# SOCEthernetPHY.net
KiCad netlist of a schematic drawn in Altium Designer
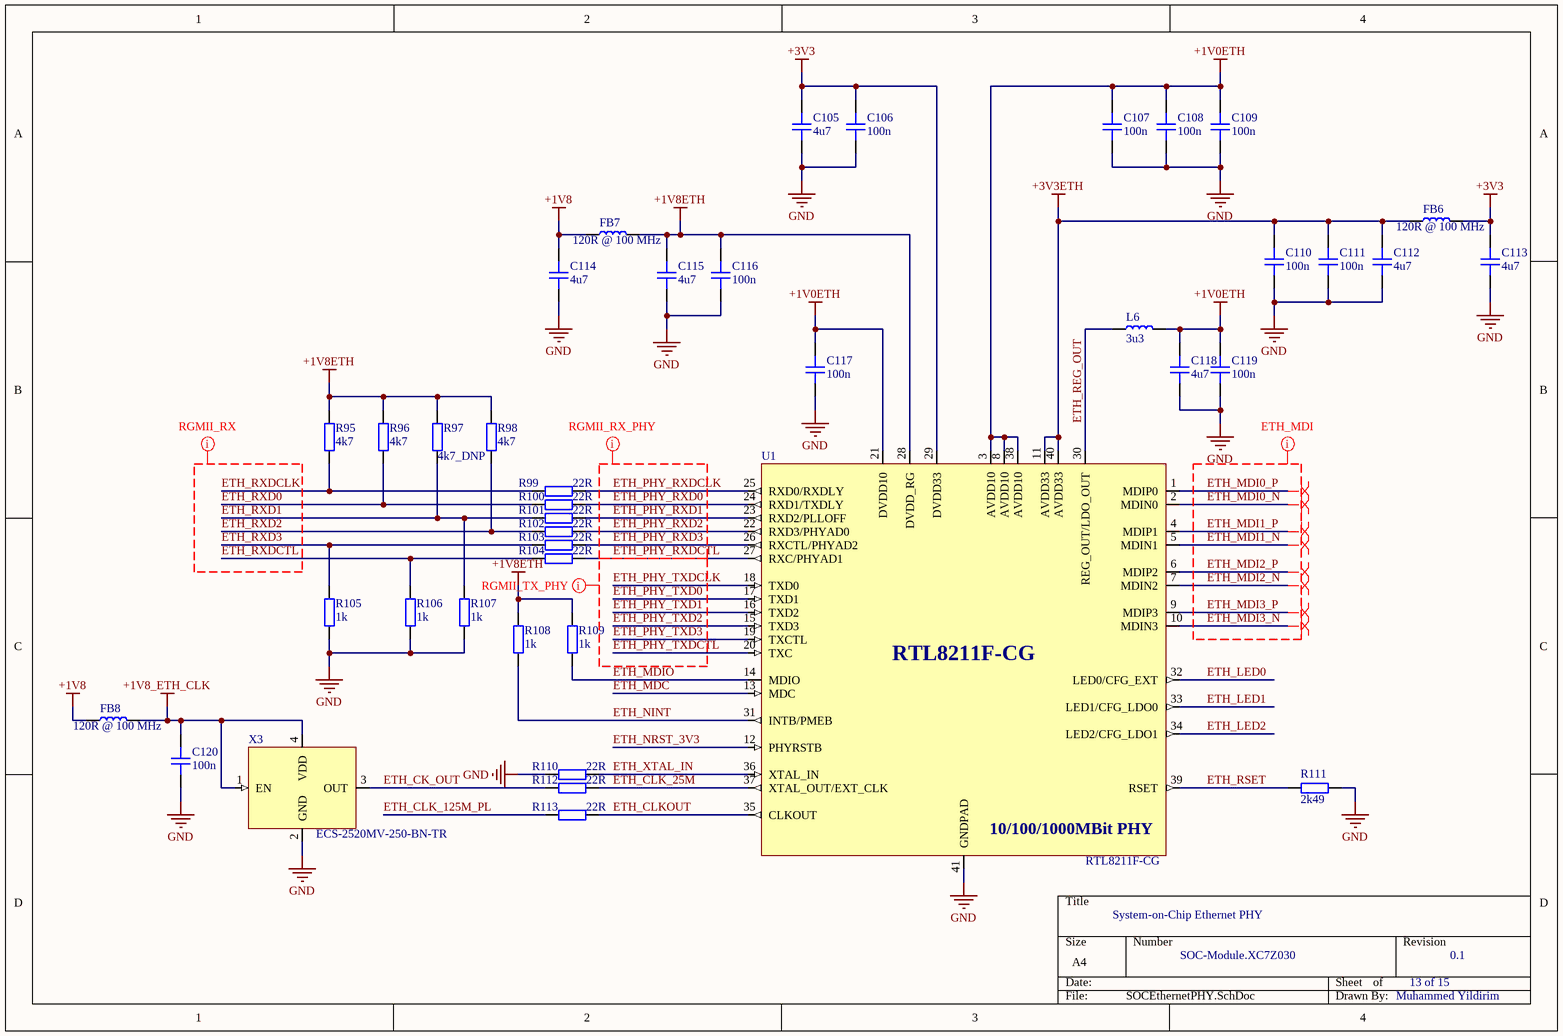
[diagram p0: SOCEthernetPHY.SchDoc]

(export (version "E")
  (design (tool "Eeschema 10.0.6"))
  (components
    (comp (ref "C105")
      (value "4u7")
      (footprint "CAP_0402")
      (description "Capacitor SMD 0402")
      (libsource (lib "Schematic-Lib-PhilsLab") (part "CAP_0402"))
    )
    (comp (ref "C106")
      (value "100n")
      (footprint "CAP_0201")
      (description "Capacitor SMD 0201")
      (libsource (lib "Schematic-Lib-PhilsLab") (part "CAP_0201"))
    )
    (comp (ref "C107")
      (value "100n")
      (footprint "CAP_0201")
      (description "Capacitor SMD 0201")
      (libsource (lib "Schematic-Lib-PhilsLab") (part "CAP_0201"))
    )
    (comp (ref "C108")
      (value "100n")
      (footprint "CAP_0201")
      (description "Capacitor SMD 0201")
      (libsource (lib "Schematic-Lib-PhilsLab") (part "CAP_0201"))
    )
    (comp (ref "C109")
      (value "100n")
      (footprint "CAP_0201")
      (description "Capacitor SMD 0201")
      (libsource (lib "Schematic-Lib-PhilsLab") (part "CAP_0201"))
    )
    (comp (ref "C110")
      (value "100n")
      (footprint "CAP_0201")
      (description "Capacitor SMD 0201")
      (libsource (lib "Schematic-Lib-PhilsLab") (part "CAP_0201"))
    )
    (comp (ref "C111")
      (value "100n")
      (footprint "CAP_0201")
      (description "Capacitor SMD 0201")
      (libsource (lib "Schematic-Lib-PhilsLab") (part "CAP_0201"))
    )
    (comp (ref "C112")
      (value "4u7")
      (footprint "CAP_0402")
      (description "Capacitor SMD 0402")
      (libsource (lib "Schematic-Lib-PhilsLab") (part "CAP_0402"))
    )
    (comp (ref "C113")
      (value "4u7")
      (footprint "CAP_0402")
      (description "Capacitor SMD 0402")
      (libsource (lib "Schematic-Lib-PhilsLab") (part "CAP_0402"))
    )
    (comp (ref "C114")
      (value "4u7")
      (footprint "CAP_0402")
      (description "Capacitor SMD 0402")
      (libsource (lib "Schematic-Lib-PhilsLab") (part "CAP_0402"))
    )
    (comp (ref "C115")
      (value "4u7")
      (footprint "CAP_0402")
      (description "Capacitor SMD 0402")
      (libsource (lib "Schematic-Lib-PhilsLab") (part "CAP_0402"))
    )
    (comp (ref "C116")
      (value "100n")
      (footprint "CAP_0201")
      (description "Capacitor SMD 0201")
      (libsource (lib "Schematic-Lib-PhilsLab") (part "CAP_0201"))
    )
    (comp (ref "C117")
      (value "100n")
      (footprint "CAP_0201")
      (description "Capacitor SMD 0201")
      (libsource (lib "Schematic-Lib-PhilsLab") (part "CAP_0201"))
    )
    (comp (ref "C118")
      (value "4u7")
      (footprint "CAP_0402")
      (description "Capacitor SMD 0402")
      (libsource (lib "Schematic-Lib-PhilsLab") (part "CAP_0402"))
    )
    (comp (ref "C119")
      (value "100n")
      (footprint "CAP_0201")
      (description "Capacitor SMD 0201")
      (libsource (lib "Schematic-Lib-PhilsLab") (part "CAP_0201"))
    )
    (comp (ref "C120")
      (value "100n")
      (footprint "CAP_0201")
      (description "Capacitor SMD 0201")
      (libsource (lib "Schematic-Lib-PhilsLab") (part "CAP_0201"))
    )
    (comp (ref "FB6")
      (value "120R @ 100 MHz")
      (footprint "Footprint-Lib-PhilsLab:IND_0201")
      (description "Inductor SMD 0201")
      (fields
        (field (name "MANUFACTURER_PART_NUMBER") "LQP03HQ56NH02D")
        (field (name "MOUSER PART NUMBER") "81-LQP03HQ56NH02D")
      )
      (libsource (lib "Schematic-Lib-PhilsLab") (part "IND_0201"))
    )
    (comp (ref "FB7")
      (value "120R @ 100 MHz")
      (footprint "Footprint-Lib-PhilsLab:IND_0201")
      (description "Inductor SMD 0201")
      (fields
        (field (name "MANUFACTURER_PART_NUMBER") "LQP03HQ56NH02D")
        (field (name "MOUSER PART NUMBER") "81-LQP03HQ56NH02D")
      )
      (libsource (lib "Schematic-Lib-PhilsLab") (part "IND_0201"))
    )
    (comp (ref "FB8")
      (value "120R @ 100 MHz")
      (footprint "Footprint-Lib-PhilsLab:IND_0201")
      (description "Inductor SMD 0201")
      (fields
        (field (name "MANUFACTURER_PART_NUMBER") "LQP03HQ56NH02D")
        (field (name "MOUSER PART NUMBER") "81-LQP03HQ56NH02D")
      )
      (libsource (lib "Schematic-Lib-PhilsLab") (part "IND_0201"))
    )
    (comp (ref "L6")
      (value "3u3")
      (footprint "IND_0402")
      (description "Inductor SMD 0402")
      (libsource (lib "Schematic-Lib-PhilsLab") (part "IND_0402"))
    )
    (comp (ref "R95")
      (value "4k7")
      (footprint "RES_0201")
      (description "Resistor SMD 0201")
      (libsource (lib "Schematic-Lib-PhilsLab") (part "RES_0201"))
    )
    (comp (ref "R96")
      (value "4k7")
      (footprint "RES_0201")
      (description "Resistor SMD 0201")
      (libsource (lib "Schematic-Lib-PhilsLab") (part "RES_0201"))
    )
    (comp (ref "R97")
      (value "4k7_DNP")
      (footprint "RES_0201")
      (description "Resistor SMD 0201")
      (libsource (lib "Schematic-Lib-PhilsLab") (part "RES_0201"))
    )
    (comp (ref "R98")
      (value "4k7")
      (footprint "RES_0201")
      (description "Resistor SMD 0201")
      (libsource (lib "Schematic-Lib-PhilsLab") (part "RES_0201"))
    )
    (comp (ref "R99")
      (value "22R")
      (footprint "RES_0201")
      (description "Resistor SMD 0201")
      (libsource (lib "Schematic-Lib-PhilsLab") (part "RES_0201"))
    )
    (comp (ref "R100")
      (value "22R")
      (footprint "RES_0201")
      (description "Resistor SMD 0201")
      (libsource (lib "Schematic-Lib-PhilsLab") (part "RES_0201"))
    )
    (comp (ref "R101")
      (value "22R")
      (footprint "RES_0201")
      (description "Resistor SMD 0201")
      (libsource (lib "Schematic-Lib-PhilsLab") (part "RES_0201"))
    )
    (comp (ref "R102")
      (value "22R")
      (footprint "RES_0201")
      (description "Resistor SMD 0201")
      (libsource (lib "Schematic-Lib-PhilsLab") (part "RES_0201"))
    )
    (comp (ref "R103")
      (value "22R")
      (footprint "RES_0201")
      (description "Resistor SMD 0201")
      (libsource (lib "Schematic-Lib-PhilsLab") (part "RES_0201"))
    )
    (comp (ref "R104")
      (value "22R")
      (footprint "RES_0201")
      (description "Resistor SMD 0201")
      (libsource (lib "Schematic-Lib-PhilsLab") (part "RES_0201"))
    )
    (comp (ref "R105")
      (value "1k")
      (footprint "RES_0201")
      (description "Resistor SMD 0201")
      (libsource (lib "Schematic-Lib-PhilsLab") (part "RES_0201"))
    )
    (comp (ref "R106")
      (value "1k")
      (footprint "RES_0201")
      (description "Resistor SMD 0201")
      (libsource (lib "Schematic-Lib-PhilsLab") (part "RES_0201"))
    )
    (comp (ref "R107")
      (value "1k")
      (footprint "RES_0201")
      (description "Resistor SMD 0201")
      (libsource (lib "Schematic-Lib-PhilsLab") (part "RES_0201"))
    )
    (comp (ref "R108")
      (value "1k")
      (footprint "RES_0201")
      (description "Resistor SMD 0201")
      (libsource (lib "Schematic-Lib-PhilsLab") (part "RES_0201"))
    )
    (comp (ref "R109")
      (value "1k")
      (footprint "RES_0201")
      (description "Resistor SMD 0201")
      (libsource (lib "Schematic-Lib-PhilsLab") (part "RES_0201"))
    )
    (comp (ref "R110")
      (value "22R")
      (footprint "RES_0201")
      (description "Resistor SMD 0201")
      (libsource (lib "Schematic-Lib-PhilsLab") (part "RES_0201"))
    )
    (comp (ref "R111")
      (value "2k49")
      (footprint "RES_0201")
      (description "Resistor SMD 0201")
      (libsource (lib "Schematic-Lib-PhilsLab") (part "RES_0201"))
    )
    (comp (ref "R112")
      (value "22R")
      (footprint "RES_0201")
      (description "Resistor SMD 0201")
      (libsource (lib "Schematic-Lib-PhilsLab") (part "RES_0201"))
    )
    (comp (ref "R113")
      (value "22R")
      (footprint "RES_0201")
      (description "Resistor SMD 0201")
      (libsource (lib "Schematic-Lib-PhilsLab") (part "RES_0201"))
    )
    (comp (ref "U1")
      (value "RTL8211F-CG")
      (footprint "QFN-40-0.4-EP")
      (description "INTEGRATED 10/100/1000M ETHERNET PRECISION TRANSCEIVER")
      (fields (field (name "MANUFACTURER") "Realtek"))
      (libsource (lib "Schematic-Lib-PhilsLab") (part "RTL8211F-CG"))
    )
    (comp (ref "X3")
      (value "ECS-2520MV-250-BN-TR")
      (footprint "XTAL_2520")
      (fields
        (field (name "MANUFACTURER") "ECS")
        (field (name "MANUFACTURER PART NUMBER") "ECS-2520MV-130-BN-TR")
      )
      (libsource (lib "Schematic-Lib-PhilsLab") (part "ECS-2520MV-130-BN-TR"))
    )
  )
  (nets
    (net (code "1") (name "+1V0ETH") (class "Default")
      (node (ref "C107") (pin "2") (pinfunction "2_2") (pintype "passive"))
      (node (ref "C108") (pin "2") (pinfunction "2_2") (pintype "passive"))
      (node (ref "C109") (pin "2") (pinfunction "2_2") (pintype "passive"))
      (node (ref "C117") (pin "2") (pinfunction "2_2") (pintype "passive"))
      (node (ref "C118") (pin "2") (pinfunction "2_2") (pintype "passive"))
      (node (ref "C119") (pin "1") (pinfunction "1_1") (pintype "passive"))
      (node (ref "L6") (pin "2") (pinfunction "2_2") (pintype "passive"))
      (node (ref "U1") (pin "21") (pinfunction "DVDD10_21") (pintype "power_in"))
      (node (ref "U1") (pin "3") (pinfunction "AVDD10_3") (pintype "power_in"))
      (node (ref "U1") (pin "38") (pinfunction "AVDD10_38") (pintype "power_in"))
      (node (ref "U1") (pin "8") (pinfunction "AVDD10_8") (pintype "power_in"))
    )
    (net (code "2") (name "+1V8") (class "Default")
      (node (ref "C114") (pin "2") (pinfunction "2_2") (pintype "passive"))
      (node (ref "FB7") (pin "1") (pinfunction "1_1") (pintype "passive"))
      (node (ref "FB8") (pin "1") (pinfunction "1_1") (pintype "passive"))
    )
    (net (code "3") (name "+1V8ETH") (class "Default")
      (node (ref "C115") (pin "2") (pinfunction "2_2") (pintype "passive"))
      (node (ref "C116") (pin "2") (pinfunction "2_2") (pintype "passive"))
      (node (ref "FB7") (pin "2") (pinfunction "2_2") (pintype "passive"))
      (node (ref "R108") (pin "1") (pinfunction "1_1") (pintype "passive"))
      (node (ref "R109") (pin "1") (pinfunction "1_1") (pintype "passive"))
      (node (ref "R95") (pin "1") (pinfunction "1_1") (pintype "passive"))
      (node (ref "R96") (pin "1") (pinfunction "1_1") (pintype "passive"))
      (node (ref "R97") (pin "1") (pinfunction "1_1") (pintype "passive"))
      (node (ref "R98") (pin "1") (pinfunction "1_1") (pintype "passive"))
      (node (ref "U1") (pin "28") (pinfunction "DVDD_RG_28") (pintype "power_in"))
    )
    (net (code "4") (name "+1V8_ETH_CLK") (class "Default")
      (node (ref "C120") (pin "1") (pinfunction "1_1") (pintype "passive"))
      (node (ref "FB8") (pin "2") (pinfunction "2_2") (pintype "passive"))
      (node (ref "X3") (pin "1") (pinfunction "EN_1") (pintype "input"))
      (node (ref "X3") (pin "4") (pinfunction "VDD_4") (pintype "power_in"))
    )
    (net (code "5") (name "+3V3") (class "Default")
      (node (ref "C105") (pin "2") (pinfunction "2_2") (pintype "passive"))
      (node (ref "C106") (pin "2") (pinfunction "2_2") (pintype "passive"))
      (node (ref "C113") (pin "2") (pinfunction "2_2") (pintype "passive"))
      (node (ref "FB6") (pin "2") (pinfunction "2_2") (pintype "passive"))
      (node (ref "U1") (pin "29") (pinfunction "DVDD33_29") (pintype "power_in"))
    )
    (net (code "6") (name "+3V3ETH") (class "Default")
      (node (ref "C110") (pin "1") (pinfunction "1_1") (pintype "passive"))
      (node (ref "C111") (pin "1") (pinfunction "1_1") (pintype "passive"))
      (node (ref "C112") (pin "2") (pinfunction "2_2") (pintype "passive"))
      (node (ref "FB6") (pin "1") (pinfunction "1_1") (pintype "passive"))
      (node (ref "U1") (pin "11") (pinfunction "AVDD33_11") (pintype "power_in"))
      (node (ref "U1") (pin "40") (pinfunction "AVDD33_40") (pintype "power_in"))
    )
    (net (code "7") (name "/ETH_CK_OUT") (class "Default")
      (node (ref "R112") (pin "1") (pinfunction "1_1") (pintype "passive"))
      (node (ref "X3") (pin "3") (pinfunction "OUT_3") (pintype "passive"))
    )
    (net (code "8") (name "/ETH_CLKOUT") (class "Default")
      (node (ref "R113") (pin "2") (pinfunction "2_2") (pintype "passive"))
      (node (ref "U1") (pin "35") (pinfunction "CLKOUT_35") (pintype "output"))
    )
    (net (code "9") (name "/ETH_CLK_25M") (class "Default")
      (node (ref "R112") (pin "2") (pinfunction "2_2") (pintype "passive"))
      (node (ref "U1") (pin "37") (pinfunction "XTAL_OUT/EXT_CLK_37") (pintype "output"))
    )
    (net (code "10") (name "/ETH_CLK_125M_PL") (class "Default")
      (node (ref "R113") (pin "1") (pinfunction "1_1") (pintype "passive"))
    )
    (net (code "11") (name "/ETH_LED0") (class "Default")
      (node (ref "U1") (pin "32") (pinfunction "LED0/CFG_EXT_32") (pintype "output"))
    )
    (net (code "12") (name "/ETH_LED1") (class "Default")
      (node (ref "U1") (pin "33") (pinfunction "LED1/CFG_LDO0_33") (pintype "output"))
    )
    (net (code "13") (name "/ETH_LED2") (class "Default")
      (node (ref "U1") (pin "34") (pinfunction "LED2/CFG_LDO1_34") (pintype "output"))
    )
    (net (code "14") (name "/ETH_MDC") (class "Default")
      (node (ref "U1") (pin "13") (pinfunction "MDC_13") (pintype "input"))
    )
    (net (code "15") (name "/ETH_MDI0_N") (class "Default")
      (node (ref "U1") (pin "2") (pinfunction "MDIN0_2") (pintype "bidirectional"))
    )
    (net (code "16") (name "/ETH_MDI0_P") (class "Default")
      (node (ref "U1") (pin "1") (pinfunction "MDIP0_1") (pintype "bidirectional"))
    )
    (net (code "17") (name "/ETH_MDI1_N") (class "Default")
      (node (ref "U1") (pin "5") (pinfunction "MDIN1_5") (pintype "bidirectional"))
    )
    (net (code "18") (name "/ETH_MDI1_P") (class "Default")
      (node (ref "U1") (pin "4") (pinfunction "MDIP1_4") (pintype "bidirectional"))
    )
    (net (code "19") (name "/ETH_MDI2_N") (class "Default")
      (node (ref "U1") (pin "7") (pinfunction "MDIN2_7") (pintype "bidirectional"))
    )
    (net (code "20") (name "/ETH_MDI2_P") (class "Default")
      (node (ref "U1") (pin "6") (pinfunction "MDIP2_6") (pintype "bidirectional"))
    )
    (net (code "21") (name "/ETH_MDI3_N") (class "Default")
      (node (ref "U1") (pin "10") (pinfunction "MDIN3_10") (pintype "bidirectional"))
    )
    (net (code "22") (name "/ETH_MDI3_P") (class "Default")
      (node (ref "U1") (pin "9") (pinfunction "MDIP3_9") (pintype "bidirectional"))
    )
    (net (code "23") (name "/ETH_MDIO") (class "Default")
      (node (ref "R109") (pin "2") (pinfunction "2_2") (pintype "passive"))
      (node (ref "U1") (pin "14") (pinfunction "MDIO_14") (pintype "bidirectional"))
    )
    (net (code "24") (name "/ETH_NINT") (class "Default")
      (node (ref "R108") (pin "2") (pinfunction "2_2") (pintype "passive"))
      (node (ref "U1") (pin "31") (pinfunction "INTB/PMEB_31") (pintype "output"))
    )
    (net (code "25") (name "/ETH_NRST_3V3") (class "Default")
      (node (ref "U1") (pin "12") (pinfunction "PHYRSTB_12") (pintype "input"))
    )
    (net (code "26") (name "/ETH_PHY_RXD0") (class "Default")
      (node (ref "R100") (pin "1") (pinfunction "1_1") (pintype "passive"))
      (node (ref "U1") (pin "24") (pinfunction "RXD1/TXDLY_24") (pintype "output"))
    )
    (net (code "27") (name "/ETH_PHY_RXD1") (class "Default")
      (node (ref "R101") (pin "1") (pinfunction "1_1") (pintype "passive"))
      (node (ref "U1") (pin "23") (pinfunction "RXD2/PLLOFF_23") (pintype "output"))
    )
    (net (code "28") (name "/ETH_PHY_RXD2") (class "Default")
      (node (ref "R102") (pin "1") (pinfunction "1_1") (pintype "passive"))
      (node (ref "U1") (pin "22") (pinfunction "RXD3/PHYAD0_22") (pintype "output"))
    )
    (net (code "29") (name "/ETH_PHY_RXD3") (class "Default")
      (node (ref "R103") (pin "1") (pinfunction "1_1") (pintype "passive"))
      (node (ref "U1") (pin "26") (pinfunction "RXCTL/PHYAD2_26") (pintype "output"))
    )
    (net (code "30") (name "/ETH_PHY_RXDCLK") (class "Default")
      (node (ref "R99") (pin "1") (pinfunction "1_1") (pintype "passive"))
      (node (ref "U1") (pin "25") (pinfunction "RXD0/RXDLY_25") (pintype "output"))
    )
    (net (code "31") (name "/ETH_PHY_RXDCTL") (class "Default")
      (node (ref "R104") (pin "1") (pinfunction "1_1") (pintype "passive"))
      (node (ref "U1") (pin "27") (pinfunction "RXC/PHYAD1_27") (pintype "output"))
    )
    (net (code "32") (name "/ETH_PHY_TXD0") (class "Default")
      (node (ref "U1") (pin "17") (pinfunction "TXD1_17") (pintype "input"))
    )
    (net (code "33") (name "/ETH_PHY_TXD1") (class "Default")
      (node (ref "U1") (pin "16") (pinfunction "TXD2_16") (pintype "input"))
    )
    (net (code "34") (name "/ETH_PHY_TXD2") (class "Default")
      (node (ref "U1") (pin "15") (pinfunction "TXD3_15") (pintype "input"))
    )
    (net (code "35") (name "/ETH_PHY_TXD3") (class "Default")
      (node (ref "U1") (pin "19") (pinfunction "TXCTL_19") (pintype "input"))
    )
    (net (code "36") (name "/ETH_PHY_TXDCLK") (class "Default")
      (node (ref "U1") (pin "18") (pinfunction "TXD0_18") (pintype "input"))
    )
    (net (code "37") (name "/ETH_PHY_TXDCTL") (class "Default")
      (node (ref "U1") (pin "20") (pinfunction "TXC_20") (pintype "input"))
    )
    (net (code "38") (name "/ETH_REG_OUT") (class "Default")
      (node (ref "L6") (pin "1") (pinfunction "1_1") (pintype "passive"))
      (node (ref "U1") (pin "30") (pinfunction "REG_OUT/LDO_OUT_30") (pintype "power_in"))
    )
    (net (code "39") (name "/ETH_RSET") (class "Default")
      (node (ref "R111") (pin "2") (pinfunction "2_2") (pintype "passive"))
      (node (ref "U1") (pin "39") (pinfunction "RSET_39") (pintype "output"))
    )
    (net (code "40") (name "/ETH_RXD0") (class "Default")
      (node (ref "R100") (pin "2") (pinfunction "2_2") (pintype "passive"))
      (node (ref "R96") (pin "2") (pinfunction "2_2") (pintype "passive"))
    )
    (net (code "41") (name "/ETH_RXD1") (class "Default")
      (node (ref "R101") (pin "2") (pinfunction "2_2") (pintype "passive"))
      (node (ref "R107") (pin "1") (pinfunction "1_1") (pintype "passive"))
      (node (ref "R97") (pin "2") (pinfunction "2_2") (pintype "passive"))
    )
    (net (code "42") (name "/ETH_RXD2") (class "Default")
      (node (ref "R102") (pin "2") (pinfunction "2_2") (pintype "passive"))
      (node (ref "R98") (pin "2") (pinfunction "2_2") (pintype "passive"))
    )
    (net (code "43") (name "/ETH_RXD3") (class "Default")
      (node (ref "R103") (pin "2") (pinfunction "2_2") (pintype "passive"))
      (node (ref "R105") (pin "1") (pinfunction "1_1") (pintype "passive"))
    )
    (net (code "44") (name "/ETH_RXDCLK") (class "Default")
      (node (ref "R95") (pin "2") (pinfunction "2_2") (pintype "passive"))
      (node (ref "R99") (pin "2") (pinfunction "2_2") (pintype "passive"))
    )
    (net (code "45") (name "/ETH_RXDCTL") (class "Default")
      (node (ref "R104") (pin "2") (pinfunction "2_2") (pintype "passive"))
      (node (ref "R106") (pin "1") (pinfunction "1_1") (pintype "passive"))
    )
    (net (code "46") (name "/ETH_XTAL_IN") (class "Default")
      (node (ref "R110") (pin "2") (pinfunction "2_2") (pintype "passive"))
      (node (ref "U1") (pin "36") (pinfunction "XTAL_IN_36") (pintype "input"))
    )
    (net (code "47") (name "GND") (class "Default")
      (node (ref "C105") (pin "1") (pinfunction "1_1") (pintype "passive"))
      (node (ref "C106") (pin "1") (pinfunction "1_1") (pintype "passive"))
      (node (ref "C107") (pin "1") (pinfunction "1_1") (pintype "passive"))
      (node (ref "C108") (pin "1") (pinfunction "1_1") (pintype "passive"))
      (node (ref "C109") (pin "1") (pinfunction "1_1") (pintype "passive"))
      (node (ref "C110") (pin "2") (pinfunction "2_2") (pintype "passive"))
      (node (ref "C111") (pin "2") (pinfunction "2_2") (pintype "passive"))
      (node (ref "C112") (pin "1") (pinfunction "1_1") (pintype "passive"))
      (node (ref "C113") (pin "1") (pinfunction "1_1") (pintype "passive"))
      (node (ref "C114") (pin "1") (pinfunction "1_1") (pintype "passive"))
      (node (ref "C115") (pin "1") (pinfunction "1_1") (pintype "passive"))
      (node (ref "C116") (pin "1") (pinfunction "1_1") (pintype "passive"))
      (node (ref "C117") (pin "1") (pinfunction "1_1") (pintype "passive"))
      (node (ref "C118") (pin "1") (pinfunction "1_1") (pintype "passive"))
      (node (ref "C119") (pin "2") (pinfunction "2_2") (pintype "passive"))
      (node (ref "C120") (pin "2") (pinfunction "2_2") (pintype "passive"))
      (node (ref "R105") (pin "2") (pinfunction "2_2") (pintype "passive"))
      (node (ref "R106") (pin "2") (pinfunction "2_2") (pintype "passive"))
      (node (ref "R107") (pin "2") (pinfunction "2_2") (pintype "passive"))
      (node (ref "R110") (pin "1") (pinfunction "1_1") (pintype "passive"))
      (node (ref "R111") (pin "1") (pinfunction "1_1") (pintype "passive"))
      (node (ref "U1") (pin "41") (pinfunction "GNDPAD_41") (pintype "power_in"))
      (node (ref "X3") (pin "2") (pinfunction "GND_2") (pintype "power_in"))
    )
  )
)
